# pmod_ssd.net
KiCad netlist of a schematic drawn in Altium Designer
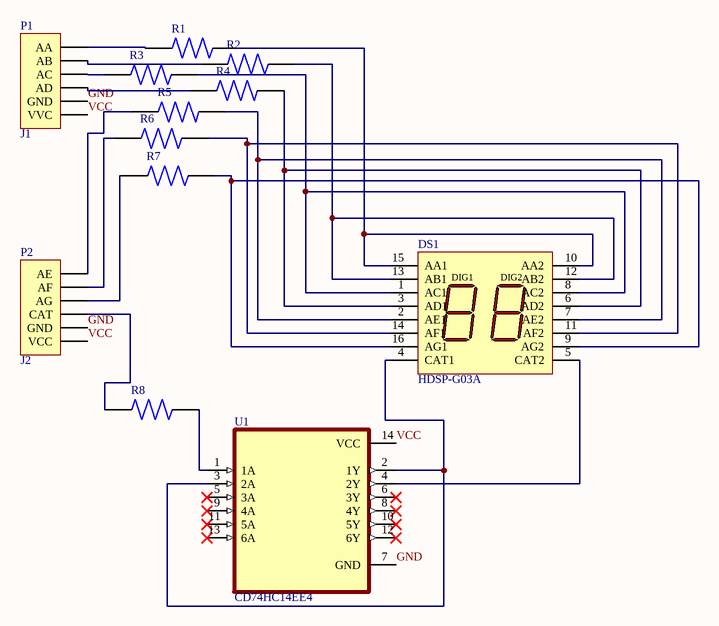
[diagram p0: pmod_ssd.SchDoc]

(export (version "E")
  (design (tool "Eeschema 10.0.6"))
  (components
    (comp (ref "DS1")
      (value "HDSP-G03A")
      (footprint "G-16")
      (description "10.16 mm 2-Digit General Purpose AlGaAs Red 7-Segment Display: CC, RH DP")
      (fields (field (name "PUBLISHER") "Altium Limited"))
      (libsource (lib "Agilent LED Display 7-Segment, 2-Digit") (part "HDSP-G03A"))
    )
    (comp (ref "P1")
      (value "J1")
      (footprint "HDR1X6H")
      (description "Header, 6-Pin, Right Angle")
      (fields (field (name "PUBLISHER") "Altium Limited"))
      (libsource (lib "Miscellaneous Connectors") (part "Header 6H"))
    )
    (comp (ref "P2")
      (value "J2")
      (footprint "HDR1X6H")
      (description "Header, 6-Pin, Right Angle")
      (fields (field (name "PUBLISHER") "Altium Limited"))
      (libsource (lib "Miscellaneous Connectors") (part "Header 6H"))
    )
    (comp (ref "R1")
      (value "5-2176327-9")
      (footprint "RESC2012X65N")
      (description "Fixed Resistor CRGP 0805 680K 1%")
      (libsource (lib "5-2176327-9") (part "5-2176327-9"))
    )
    (comp (ref "R2")
      (value "5-2176327-9")
      (footprint "RESC2012X65N")
      (description "Fixed Resistor CRGP 0805 680K 1%")
      (libsource (lib "5-2176327-9") (part "5-2176327-9"))
    )
    (comp (ref "R3")
      (value "5-2176327-9")
      (footprint "RESC2012X65N")
      (description "Fixed Resistor CRGP 0805 680K 1%")
      (libsource (lib "5-2176327-9") (part "5-2176327-9"))
    )
    (comp (ref "R4")
      (value "5-2176327-9")
      (footprint "RESC2012X65N")
      (description "Fixed Resistor CRGP 0805 680K 1%")
      (libsource (lib "5-2176327-9") (part "5-2176327-9"))
    )
    (comp (ref "R5")
      (value "5-2176327-9")
      (footprint "RESC2012X65N")
      (description "Fixed Resistor CRGP 0805 680K 1%")
      (libsource (lib "5-2176327-9") (part "5-2176327-9"))
    )
    (comp (ref "R6")
      (value "5-2176327-9")
      (footprint "RESC2012X65N")
      (description "Fixed Resistor CRGP 0805 680K 1%")
      (libsource (lib "5-2176327-9") (part "5-2176327-9"))
    )
    (comp (ref "R7")
      (value "5-2176327-9")
      (footprint "RESC2012X65N")
      (description "Fixed Resistor CRGP 0805 680K 1%")
      (libsource (lib "5-2176327-9") (part "5-2176327-9"))
    )
    (comp (ref "R8")
      (value "5-2176327-9")
      (footprint "RESC2012X65N")
      (description "Fixed Resistor CRGP 0805 680K 1%")
      (libsource (lib "5-2176327-9") (part "5-2176327-9"))
    )
    (comp (ref "U1")
      (value "CD74HC14EE4")
      (footprint "DIP794W45P254L1969H508Q14")
      (description "High Speed CMOS Logic Hex Schmitt-Triggered Inverters 14-PDIP -55 to 125")
      (fields (field (name "MF") "Texas Instruments"))
      (libsource (lib "CD74HC14EE4") (part "CD74HC14EE4"))
    )
  )
  (nets
    (net (code "2") (name "/GND") (class "Default")
      (node (ref "P1") (pin "5") (pinfunction "GND_5") (pintype "passive"))
      (node (ref "P2") (pin "5") (pinfunction "GND_5") (pintype "passive"))
      (node (ref "U1") (pin "7") (pinfunction "GND_7") (pintype "power_in"))
    )
    (net (code "3") (name "/VCC") (class "Default")
      (node (ref "P1") (pin "6") (pinfunction "VVC_6") (pintype "passive"))
      (node (ref "P2") (pin "6") (pinfunction "VVC_6") (pintype "passive"))
      (node (ref "U1") (pin "14") (pinfunction "VCC_14") (pintype "power_in"))
    )
    (net (code "4") (name "Net-(DS1-AA1)") (class "Default")
      (node (ref "DS1") (pin "10") (pinfunction "AA2_10") (pintype "passive"))
      (node (ref "DS1") (pin "15") (pinfunction "AA1_15") (pintype "passive"))
      (node (ref "R1") (pin "2") (pinfunction "2_2") (pintype "passive"))
    )
    (net (code "5") (name "Net-(DS1-AB1)") (class "Default")
      (node (ref "DS1") (pin "12") (pinfunction "AB2_12") (pintype "passive"))
      (node (ref "DS1") (pin "13") (pinfunction "AB1_13") (pintype "passive"))
      (node (ref "R2") (pin "2") (pinfunction "2_2") (pintype "passive"))
    )
    (net (code "6") (name "Net-(DS1-AC1)") (class "Default")
      (node (ref "DS1") (pin "1") (pinfunction "AC1_1") (pintype "passive"))
      (node (ref "DS1") (pin "8") (pinfunction "AC2_8") (pintype "passive"))
      (node (ref "R3") (pin "2") (pinfunction "2_2") (pintype "passive"))
    )
    (net (code "7") (name "Net-(DS1-AD1)") (class "Default")
      (node (ref "DS1") (pin "3") (pinfunction "AD1_3") (pintype "passive"))
      (node (ref "DS1") (pin "6") (pinfunction "AD2_6") (pintype "passive"))
      (node (ref "R4") (pin "2") (pinfunction "2_2") (pintype "passive"))
    )
    (net (code "8") (name "Net-(DS1-AE1)") (class "Default")
      (node (ref "DS1") (pin "2") (pinfunction "AE1_2") (pintype "passive"))
      (node (ref "DS1") (pin "7") (pinfunction "AE2_7") (pintype "passive"))
      (node (ref "R5") (pin "2") (pinfunction "2_2") (pintype "passive"))
    )
    (net (code "9") (name "Net-(DS1-AF1)") (class "Default")
      (node (ref "DS1") (pin "11") (pinfunction "AF2_11") (pintype "passive"))
      (node (ref "DS1") (pin "14") (pinfunction "AF1_14") (pintype "passive"))
      (node (ref "R6") (pin "2") (pinfunction "2_2") (pintype "passive"))
    )
    (net (code "10") (name "Net-(DS1-AG1)") (class "Default")
      (node (ref "DS1") (pin "16") (pinfunction "AG1_16") (pintype "passive"))
      (node (ref "DS1") (pin "9") (pinfunction "AG2_9") (pintype "passive"))
      (node (ref "R7") (pin "2") (pinfunction "2_2") (pintype "passive"))
    )
    (net (code "11") (name "Net-(DS1-CAT1)") (class "Default")
      (node (ref "DS1") (pin "4") (pinfunction "CAT1_4") (pintype "passive"))
      (node (ref "U1") (pin "2") (pinfunction "1Y_2") (pintype "output"))
      (node (ref "U1") (pin "3") (pinfunction "2A_3") (pintype "input"))
    )
    (net (code "12") (name "Net-(DS1-CAT2)") (class "Default")
      (node (ref "DS1") (pin "5") (pinfunction "CAT2_5") (pintype "passive"))
      (node (ref "U1") (pin "4") (pinfunction "2Y_4") (pintype "output"))
    )
    (net (code "13") (name "Net-(P1-AA)") (class "Default")
      (node (ref "P1") (pin "1") (pinfunction "AA_1") (pintype "passive"))
      (node (ref "R1") (pin "1") (pinfunction "1_1") (pintype "passive"))
    )
    (net (code "14") (name "Net-(P1-AB)") (class "Default")
      (node (ref "P1") (pin "2") (pinfunction "AB_2") (pintype "passive"))
      (node (ref "R2") (pin "1") (pinfunction "1_1") (pintype "passive"))
    )
    (net (code "15") (name "Net-(P1-AC)") (class "Default")
      (node (ref "P1") (pin "3") (pinfunction "AC_3") (pintype "passive"))
      (node (ref "R3") (pin "1") (pinfunction "1_1") (pintype "passive"))
    )
    (net (code "16") (name "Net-(P1-AD)") (class "Default")
      (node (ref "P1") (pin "4") (pinfunction "AD_4") (pintype "passive"))
      (node (ref "R4") (pin "1") (pinfunction "1_1") (pintype "passive"))
    )
    (net (code "17") (name "Net-(P2-AA)") (class "Default")
      (node (ref "P2") (pin "1") (pinfunction "AA_1") (pintype "passive"))
      (node (ref "R5") (pin "1") (pinfunction "1_1") (pintype "passive"))
    )
    (net (code "18") (name "Net-(P2-AB)") (class "Default")
      (node (ref "P2") (pin "2") (pinfunction "AB_2") (pintype "passive"))
      (node (ref "R6") (pin "1") (pinfunction "1_1") (pintype "passive"))
    )
    (net (code "19") (name "Net-(P2-AC)") (class "Default")
      (node (ref "P2") (pin "3") (pinfunction "AC_3") (pintype "passive"))
      (node (ref "R7") (pin "1") (pinfunction "1_1") (pintype "passive"))
    )
    (net (code "20") (name "Net-(P2-AD)") (class "Default")
      (node (ref "P2") (pin "4") (pinfunction "AD_4") (pintype "passive"))
      (node (ref "R8") (pin "1") (pinfunction "1_1") (pintype "passive"))
    )
    (net (code "21") (name "Net-(U1-1A)") (class "Default")
      (node (ref "R8") (pin "2") (pinfunction "2_2") (pintype "passive"))
      (node (ref "U1") (pin "1") (pinfunction "1A_1") (pintype "input"))
    )
    (net (code "22") (name "unconnected-(U1-3A-Pad5)") (class "Default")
      (node (ref "U1") (pin "5") (pinfunction "3A_5") (pintype "input+no_connect"))
    )
    (net (code "23") (name "unconnected-(U1-3Y-Pad6)") (class "Default")
      (node (ref "U1") (pin "6") (pinfunction "3Y_6") (pintype "output+no_connect"))
    )
    (net (code "24") (name "unconnected-(U1-4A-Pad9)") (class "Default")
      (node (ref "U1") (pin "9") (pinfunction "4A_9") (pintype "input+no_connect"))
    )
    (net (code "25") (name "unconnected-(U1-4Y-Pad8)") (class "Default")
      (node (ref "U1") (pin "8") (pinfunction "4Y_8") (pintype "output+no_connect"))
    )
    (net (code "26") (name "unconnected-(U1-5A-Pad11)") (class "Default")
      (node (ref "U1") (pin "11") (pinfunction "5A_11") (pintype "input+no_connect"))
    )
    (net (code "27") (name "unconnected-(U1-5Y-Pad10)") (class "Default")
      (node (ref "U1") (pin "10") (pinfunction "5Y_10") (pintype "output+no_connect"))
    )
    (net (code "28") (name "unconnected-(U1-6A-Pad13)") (class "Default")
      (node (ref "U1") (pin "13") (pinfunction "6A_13") (pintype "input+no_connect"))
    )
    (net (code "29") (name "unconnected-(U1-6Y-Pad12)") (class "Default")
      (node (ref "U1") (pin "12") (pinfunction "6Y_12") (pintype "output+no_connect"))
    )
  )
)
